# LAN8870_PINOUT.net
KiCad netlist of a schematic drawn in Altium Designer
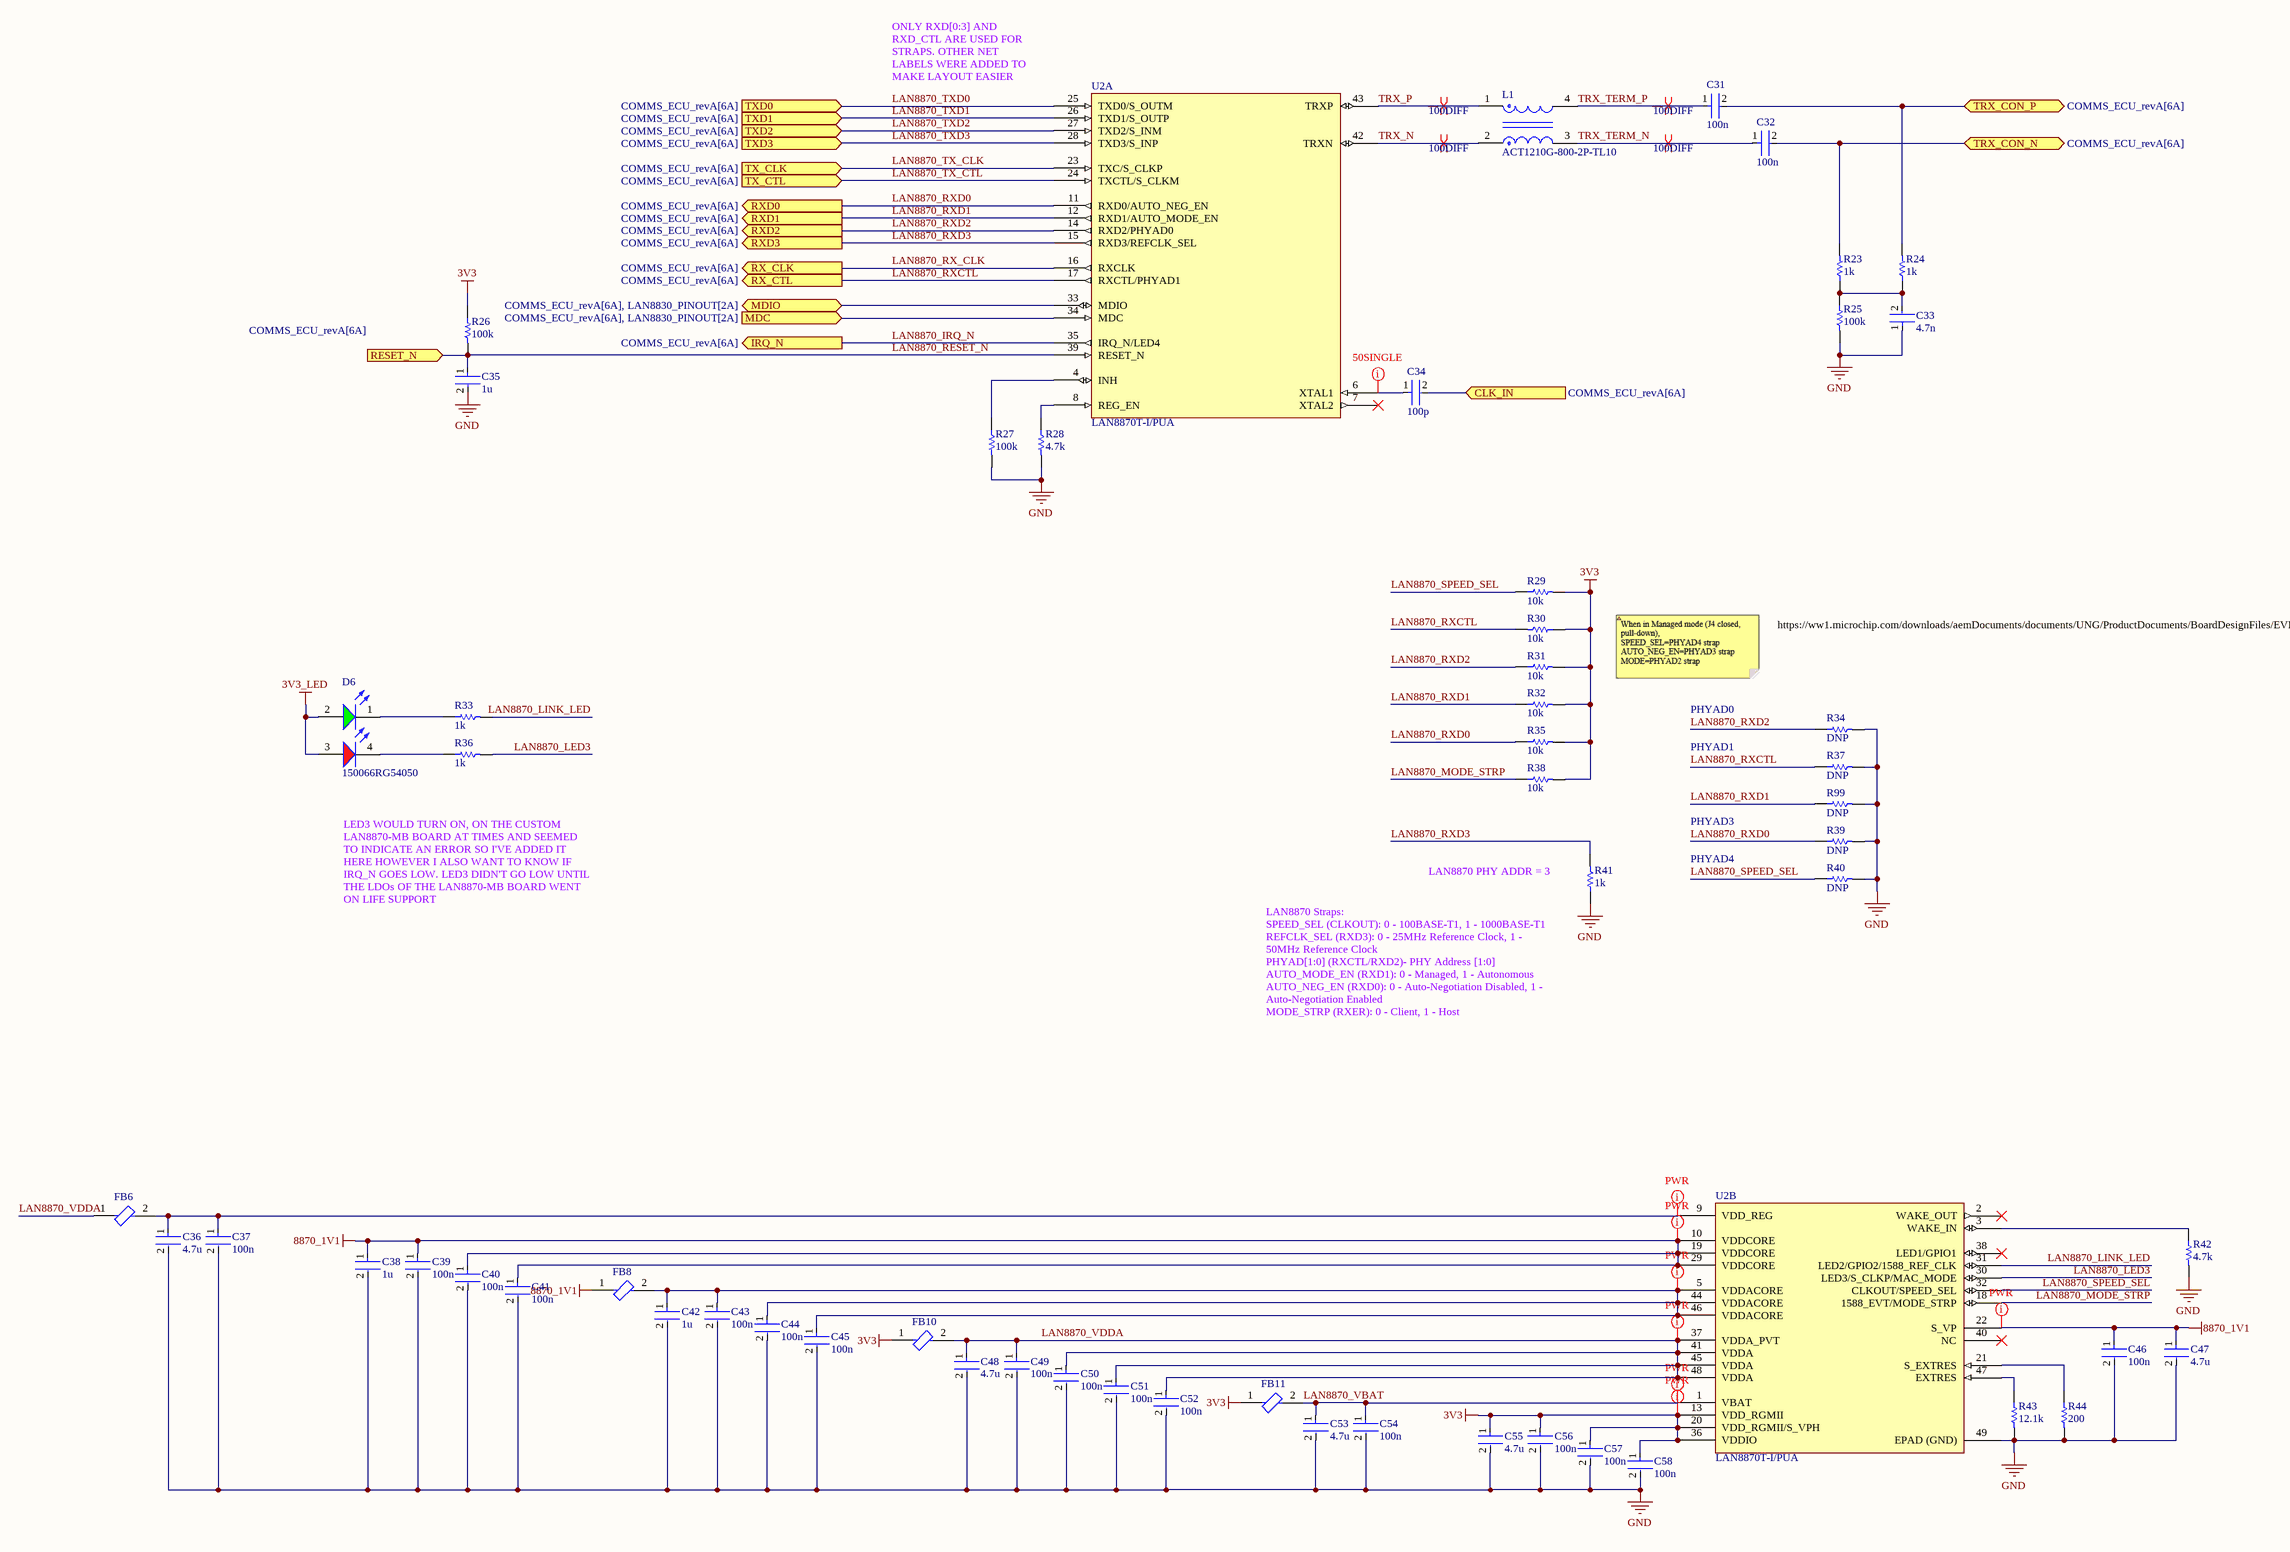
[diagram p0: LAN8870_PINOUT.SchDoc]

(export (version "E")
  (design (tool "Eeschema 10.0.6"))
  (components
    (comp (ref "C31")
      (value "100n")
      (footprint "FP-0402-L_1_0_0_05-W_0_5-IPC_A")
      (description "LARGE PADS, 0402 CAP, CHANGE COMMENT TO MATCH REAL P/N")
      (libsource (lib "Space Concordia") (part "b4654b650e69147ec39a6b967a45e02"))
    )
    (comp (ref "C32")
      (value "100n")
      (footprint "FP-0402-L_1_0_0_05-W_0_5-IPC_A")
      (description "LARGE PADS, 0402 CAP, CHANGE COMMENT TO MATCH REAL P/N")
      (libsource (lib "Space Concordia") (part "b4654b650e69147ec39a6b967a45e02"))
    )
    (comp (ref "C33")
      (value "4.7n")
      (footprint "FP-0402-L_1_0_0_05-W_0_5-IPC_A")
      (description "LARGE PADS, 0402 CAP, CHANGE COMMENT TO MATCH REAL P/N")
      (libsource (lib "Space Concordia") (part "b4654b650e69147ec39a6b967a45e02"))
    )
    (comp (ref "C34")
      (value "100p")
      (footprint "FP-0402-L_1_0_0_05-W_0_5-IPC_A")
      (description "LARGE PADS, 0402 CAP, CHANGE COMMENT TO MATCH REAL P/N")
      (libsource (lib "Space Concordia") (part "b4654b650e69147ec39a6b967a45e02"))
    )
    (comp (ref "C35")
      (value "1u")
      (footprint "FP-0402-L_1_0_0_05-W_0_5-IPC_A")
      (description "LARGE PADS, 0402 CAP, CHANGE COMMENT TO MATCH REAL P/N")
      (libsource (lib "Space Concordia") (part "b4654b650e69147ec39a6b967a45e02"))
    )
    (comp (ref "C36")
      (value "4.7u")
      (footprint "FP-0402-L_1_0_0_05-W_0_5-IPC_A")
      (description "LARGE PADS, 0402 CAP, CHANGE COMMENT TO MATCH REAL P/N")
      (libsource (lib "Space Concordia") (part "b4654b650e69147ec39a6b967a45e02"))
    )
    (comp (ref "C37")
      (value "100n")
      (footprint "FP-0402-L_1_0_0_05-W_0_5-IPC_A")
      (description "LARGE PADS, 0402 CAP, CHANGE COMMENT TO MATCH REAL P/N")
      (libsource (lib "Space Concordia") (part "b4654b650e69147ec39a6b967a45e02"))
    )
    (comp (ref "C38")
      (value "1u")
      (footprint "FP-0402-L_1_0_0_05-W_0_5-IPC_A")
      (description "LARGE PADS, 0402 CAP, CHANGE COMMENT TO MATCH REAL P/N")
      (libsource (lib "Space Concordia") (part "b4654b650e69147ec39a6b967a45e02"))
    )
    (comp (ref "C39")
      (value "100n")
      (footprint "FP-0402-L_1_0_0_05-W_0_5-IPC_A")
      (description "LARGE PADS, 0402 CAP, CHANGE COMMENT TO MATCH REAL P/N")
      (libsource (lib "Space Concordia") (part "b4654b650e69147ec39a6b967a45e02"))
    )
    (comp (ref "C40")
      (value "100n")
      (footprint "FP-0402-L_1_0_0_05-W_0_5-IPC_A")
      (description "LARGE PADS, 0402 CAP, CHANGE COMMENT TO MATCH REAL P/N")
      (libsource (lib "Space Concordia") (part "b4654b650e69147ec39a6b967a45e02"))
    )
    (comp (ref "C41")
      (value "100n")
      (footprint "FP-0402-L_1_0_0_05-W_0_5-IPC_A")
      (description "LARGE PADS, 0402 CAP, CHANGE COMMENT TO MATCH REAL P/N")
      (libsource (lib "Space Concordia") (part "b4654b650e69147ec39a6b967a45e02"))
    )
    (comp (ref "C42")
      (value "1u")
      (footprint "FP-0402-L_1_0_0_05-W_0_5-IPC_A")
      (description "LARGE PADS, 0402 CAP, CHANGE COMMENT TO MATCH REAL P/N")
      (libsource (lib "Space Concordia") (part "b4654b650e69147ec39a6b967a45e02"))
    )
    (comp (ref "C43")
      (value "100n")
      (footprint "FP-0402-L_1_0_0_05-W_0_5-IPC_A")
      (description "LARGE PADS, 0402 CAP, CHANGE COMMENT TO MATCH REAL P/N")
      (libsource (lib "Space Concordia") (part "b4654b650e69147ec39a6b967a45e02"))
    )
    (comp (ref "C44")
      (value "100n")
      (footprint "FP-0402-L_1_0_0_05-W_0_5-IPC_A")
      (description "LARGE PADS, 0402 CAP, CHANGE COMMENT TO MATCH REAL P/N")
      (libsource (lib "Space Concordia") (part "b4654b650e69147ec39a6b967a45e02"))
    )
    (comp (ref "C45")
      (value "100n")
      (footprint "FP-0402-L_1_0_0_05-W_0_5-IPC_A")
      (description "LARGE PADS, 0402 CAP, CHANGE COMMENT TO MATCH REAL P/N")
      (libsource (lib "Space Concordia") (part "b4654b650e69147ec39a6b967a45e02"))
    )
    (comp (ref "C46")
      (value "100n")
      (footprint "FP-0402-L_1_0_0_05-W_0_5-IPC_A")
      (description "LARGE PADS, 0402 CAP, CHANGE COMMENT TO MATCH REAL P/N")
      (libsource (lib "Space Concordia") (part "b4654b650e69147ec39a6b967a45e02"))
    )
    (comp (ref "C47")
      (value "4.7u")
      (footprint "FP-0402-L_1_0_0_05-W_0_5-IPC_A")
      (description "LARGE PADS, 0402 CAP, CHANGE COMMENT TO MATCH REAL P/N")
      (libsource (lib "Space Concordia") (part "b4654b650e69147ec39a6b967a45e02"))
    )
    (comp (ref "C48")
      (value "4.7u")
      (footprint "FP-0402-L_1_0_0_05-W_0_5-IPC_A")
      (description "LARGE PADS, 0402 CAP, CHANGE COMMENT TO MATCH REAL P/N")
      (libsource (lib "Space Concordia") (part "b4654b650e69147ec39a6b967a45e02"))
    )
    (comp (ref "C49")
      (value "100n")
      (footprint "FP-0402-L_1_0_0_05-W_0_5-IPC_A")
      (description "LARGE PADS, 0402 CAP, CHANGE COMMENT TO MATCH REAL P/N")
      (libsource (lib "Space Concordia") (part "b4654b650e69147ec39a6b967a45e02"))
    )
    (comp (ref "C50")
      (value "100n")
      (footprint "FP-0402-L_1_0_0_05-W_0_5-IPC_A")
      (description "LARGE PADS, 0402 CAP, CHANGE COMMENT TO MATCH REAL P/N")
      (libsource (lib "Space Concordia") (part "b4654b650e69147ec39a6b967a45e02"))
    )
    (comp (ref "C51")
      (value "100n")
      (footprint "FP-0402-L_1_0_0_05-W_0_5-IPC_A")
      (description "LARGE PADS, 0402 CAP, CHANGE COMMENT TO MATCH REAL P/N")
      (libsource (lib "Space Concordia") (part "b4654b650e69147ec39a6b967a45e02"))
    )
    (comp (ref "C52")
      (value "100n")
      (footprint "FP-0402-L_1_0_0_05-W_0_5-IPC_A")
      (description "LARGE PADS, 0402 CAP, CHANGE COMMENT TO MATCH REAL P/N")
      (libsource (lib "Space Concordia") (part "b4654b650e69147ec39a6b967a45e02"))
    )
    (comp (ref "C53")
      (value "4.7u")
      (footprint "FP-0402-L_1_0_0_05-W_0_5-IPC_A")
      (description "LARGE PADS, 0402 CAP, CHANGE COMMENT TO MATCH REAL P/N")
      (libsource (lib "Space Concordia") (part "b4654b650e69147ec39a6b967a45e02"))
    )
    (comp (ref "C54")
      (value "100n")
      (footprint "FP-0402-L_1_0_0_05-W_0_5-IPC_A")
      (description "LARGE PADS, 0402 CAP, CHANGE COMMENT TO MATCH REAL P/N")
      (libsource (lib "Space Concordia") (part "b4654b650e69147ec39a6b967a45e02"))
    )
    (comp (ref "C55")
      (value "4.7u")
      (footprint "FP-0402-L_1_0_0_05-W_0_5-IPC_A")
      (description "LARGE PADS, 0402 CAP, CHANGE COMMENT TO MATCH REAL P/N")
      (libsource (lib "Space Concordia") (part "b4654b650e69147ec39a6b967a45e02"))
    )
    (comp (ref "C56")
      (value "100n")
      (footprint "FP-0402-L_1_0_0_05-W_0_5-IPC_A")
      (description "LARGE PADS, 0402 CAP, CHANGE COMMENT TO MATCH REAL P/N")
      (libsource (lib "Space Concordia") (part "b4654b650e69147ec39a6b967a45e02"))
    )
    (comp (ref "C57")
      (value "100n")
      (footprint "FP-0402-L_1_0_0_05-W_0_5-IPC_A")
      (description "LARGE PADS, 0402 CAP, CHANGE COMMENT TO MATCH REAL P/N")
      (libsource (lib "Space Concordia") (part "b4654b650e69147ec39a6b967a45e02"))
    )
    (comp (ref "C58")
      (value "100n")
      (footprint "FP-0402-L_1_0_0_05-W_0_5-IPC_A")
      (description "LARGE PADS, 0402 CAP, CHANGE COMMENT TO MATCH REAL P/N")
      (libsource (lib "Space Concordia") (part "b4654b650e69147ec39a6b967a45e02"))
    )
    (comp (ref "D6")
      (value "150066RG54050")
      (footprint "WL-SBCD_0606")
      (description "Led, Red/Grn, 180Mcd/230Mcd, 624Nm/525Nm Rohs Compliant: Yes")
      (fields (field (name "SOURCE") "rgled.SchLib"))
      (libsource (lib "Space Concordia") (part "CMP-004-00034-2"))
    )
    (comp (ref "FB6")
      (value "BLM18KG331SH1D")
      (footprint "FP-BLM18-0_15-t0_8-IPC_B")
      (description "Chip Ferrite Bead, 0603, 330Ω @ 100MHz, 0.08Ω, 25%, 1.7A")
      (libsource (lib "Altium Content Vault") (part "5f30dd21d616792df468990f7003faa"))
    )
    (comp (ref "FB8")
      (value "BLM18KG331SH1D")
      (footprint "FP-BLM18-0_15-t0_8-IPC_B")
      (description "Chip Ferrite Bead, 0603, 330Ω @ 100MHz, 0.08Ω, 25%, 1.7A")
      (libsource (lib "Altium Content Vault") (part "5f30dd21d616792df468990f7003faa"))
    )
    (comp (ref "FB10")
      (value "BLM18KG331SH1D")
      (footprint "FP-BLM18-0_15-t0_8-IPC_B")
      (description "Chip Ferrite Bead, 0603, 330Ω @ 100MHz, 0.08Ω, 25%, 1.7A")
      (libsource (lib "Altium Content Vault") (part "5f30dd21d616792df468990f7003faa"))
    )
    (comp (ref "FB11")
      (value "BLM18KG331SH1D")
      (footprint "FP-BLM18-0_15-t0_8-IPC_B")
      (description "Chip Ferrite Bead, 0603, 330Ω @ 100MHz, 0.08Ω, 25%, 1.7A")
      (libsource (lib "Altium Content Vault") (part "5f30dd21d616792df468990f7003faa"))
    )
    (comp (ref "L1")
      (value "ACT1210G-800-2P-TL10")
      (footprint "FP-ACT1210G-800-2P-TL10-MFG")
      (description "CMC 80UH 70MA 2LN 3.8KOHM SMD")
      (libsource (lib "Altium Content Vault") (part "b4b74a627ea9af473eaab86227aab92"))
    )
    (comp (ref "R23")
      (value "1k")
      (footprint "R0603B")
      (description "Resistor")
      (libsource (lib "Space Concordia") (part "Resistor"))
    )
    (comp (ref "R24")
      (value "1k")
      (footprint "R0603B")
      (description "Resistor")
      (libsource (lib "Space Concordia") (part "Resistor"))
    )
    (comp (ref "R25")
      (value "100k")
      (footprint "R0603B")
      (description "Resistor")
      (libsource (lib "Space Concordia") (part "Resistor"))
    )
    (comp (ref "R26")
      (value "100k")
      (footprint "R0603B")
      (description "Resistor")
      (libsource (lib "Space Concordia") (part "Resistor"))
    )
    (comp (ref "R27")
      (value "100k")
      (footprint "R0603B")
      (description "Resistor")
      (libsource (lib "Space Concordia") (part "Resistor"))
    )
    (comp (ref "R28")
      (value "4.7k")
      (footprint "R0603B")
      (description "Resistor")
      (libsource (lib "Space Concordia") (part "Resistor"))
    )
    (comp (ref "R29")
      (value "10k")
      (footprint "R0603B")
      (description "Resistor")
      (libsource (lib "Space Concordia") (part "Resistor"))
    )
    (comp (ref "R30")
      (value "10k")
      (footprint "R0603B")
      (description "Resistor")
      (libsource (lib "Space Concordia") (part "Resistor"))
    )
    (comp (ref "R31")
      (value "10k")
      (footprint "R0603B")
      (description "Resistor")
      (libsource (lib "Space Concordia") (part "Resistor"))
    )
    (comp (ref "R32")
      (value "10k")
      (footprint "R0603B")
      (description "Resistor")
      (libsource (lib "Space Concordia") (part "Resistor"))
    )
    (comp (ref "R33")
      (value "1k")
      (footprint "R0603B")
      (description "Resistor")
      (libsource (lib "Space Concordia") (part "Resistor"))
    )
    (comp (ref "R34")
      (value "DNP")
      (footprint "R0603B")
      (description "Resistor")
      (libsource (lib "Space Concordia") (part "Resistor"))
    )
    (comp (ref "R35")
      (value "10k")
      (footprint "R0603B")
      (description "Resistor")
      (libsource (lib "Space Concordia") (part "Resistor"))
    )
    (comp (ref "R36")
      (value "1k")
      (footprint "R0603B")
      (description "Resistor")
      (libsource (lib "Space Concordia") (part "Resistor"))
    )
    (comp (ref "R37")
      (value "DNP")
      (footprint "R0603B")
      (description "Resistor")
      (libsource (lib "Space Concordia") (part "Resistor"))
    )
    (comp (ref "R38")
      (value "10k")
      (footprint "R0603B")
      (description "Resistor")
      (libsource (lib "Space Concordia") (part "Resistor"))
    )
    (comp (ref "R39")
      (value "DNP")
      (footprint "R0603B")
      (description "Resistor")
      (libsource (lib "Space Concordia") (part "Resistor"))
    )
    (comp (ref "R40")
      (value "DNP")
      (footprint "R0603B")
      (description "Resistor")
      (libsource (lib "Space Concordia") (part "Resistor"))
    )
    (comp (ref "R41")
      (value "1k")
      (footprint "R0603B")
      (description "Resistor")
      (libsource (lib "Space Concordia") (part "Resistor"))
    )
    (comp (ref "R42")
      (value "4.7k")
      (footprint "R0603B")
      (description "Resistor")
      (libsource (lib "Space Concordia") (part "Resistor"))
    )
    (comp (ref "R43")
      (value "12.1k")
      (footprint "R0603B")
      (description "Resistor")
      (libsource (lib "Space Concordia") (part "Resistor"))
    )
    (comp (ref "R44")
      (value "200")
      (footprint "R0603B")
      (description "Resistor")
      (libsource (lib "Space Concordia") (part "Resistor"))
    )
    (comp (ref "R99")
      (value "DNP")
      (footprint "R0603B")
      (description "Resistor")
      (libsource (lib "Space Concordia") (part "Resistor"))
    )
    (comp (ref "U2")
      (value "LAN8870T-I/PUA")
      (footprint "QFN50P700X700X100_HS-49N")
      (description "100/1000BASE-T1 Rgmii/sgmii Phy")
      (libsource (lib "Space Concordia") (part "LAN8870T-I_PUA"))
    )
  )
  (nets
    (net (code "1") (name "/CLK_IN") (class "Default")
      (node (ref "C34") (pin "2") (pinfunction "2_2") (pintype "passive"))
    )
    (net (code "2") (name "/LAN8870_IRQ_N") (class "Default")
      (node (ref "U2") (pin "35") (pinfunction "IRQ_N/LED4_35") (pintype "output"))
    )
    (net (code "3") (name "/LAN8870_LED3") (class "Default")
      (node (ref "R36") (pin "2") (pinfunction "2_2") (pintype "passive"))
      (node (ref "U2") (pin "30") (pinfunction "LED3/S_CLKP/MAC_MODE_30") (pintype "bidirectional"))
    )
    (net (code "4") (name "/LAN8870_LINK_LED") (class "Default")
      (node (ref "R33") (pin "2") (pinfunction "2_2") (pintype "passive"))
      (node (ref "U2") (pin "31") (pinfunction "LED2/GPIO2/1588_REF_CLK_31") (pintype "bidirectional"))
    )
    (net (code "5") (name "/LAN8870_MODE_STRP") (class "Default")
      (node (ref "R38") (pin "1") (pinfunction "1_1") (pintype "passive"))
      (node (ref "U2") (pin "18") (pinfunction "1588_EVT/MODE_STRP_18") (pintype "bidirectional"))
    )
    (net (code "6") (name "/LAN8870_RESET_N") (class "Default")
      (node (ref "C35") (pin "1") (pinfunction "1_1") (pintype "passive"))
      (node (ref "R26") (pin "2") (pinfunction "2_2") (pintype "passive"))
      (node (ref "U2") (pin "39") (pinfunction "RESET_N_39") (pintype "input"))
    )
    (net (code "7") (name "/LAN8870_RXCTL") (class "Default")
      (node (ref "R30") (pin "2") (pinfunction "2_2") (pintype "passive"))
      (node (ref "R37") (pin "1") (pinfunction "1_1") (pintype "passive"))
      (node (ref "U2") (pin "17") (pinfunction "RXCTL/PHYAD1_17") (pintype "output"))
    )
    (net (code "8") (name "/LAN8870_RXD0") (class "Default")
      (node (ref "R35") (pin "1") (pinfunction "1_1") (pintype "passive"))
      (node (ref "R39") (pin "1") (pinfunction "1_1") (pintype "passive"))
      (node (ref "U2") (pin "11") (pinfunction "RXD0/AUTO_NEG_EN_11") (pintype "output"))
    )
    (net (code "9") (name "/LAN8870_RXD1") (class "Default")
      (node (ref "R32") (pin "1") (pinfunction "1_1") (pintype "passive"))
      (node (ref "R99") (pin "1") (pinfunction "1_1") (pintype "passive"))
      (node (ref "U2") (pin "12") (pinfunction "RXD1/AUTO_MODE_EN_12") (pintype "output"))
    )
    (net (code "10") (name "/LAN8870_RXD2") (class "Default")
      (node (ref "R31") (pin "1") (pinfunction "1_1") (pintype "passive"))
      (node (ref "R34") (pin "1") (pinfunction "1_1") (pintype "passive"))
      (node (ref "U2") (pin "14") (pinfunction "RXD2/PHYAD0_14") (pintype "output"))
    )
    (net (code "11") (name "/LAN8870_RXD3") (class "Default")
      (node (ref "R41") (pin "2") (pinfunction "2_2") (pintype "passive"))
      (node (ref "U2") (pin "15") (pinfunction "RXD3/REFCLK_SEL_15") (pintype "output"))
    )
    (net (code "12") (name "/LAN8870_RX_CLK") (class "Default")
      (node (ref "U2") (pin "16") (pinfunction "RXCLK_16") (pintype "output"))
    )
    (net (code "13") (name "/LAN8870_SPEED_SEL") (class "Default")
      (node (ref "R29") (pin "1") (pinfunction "1_1") (pintype "passive"))
      (node (ref "R40") (pin "1") (pinfunction "1_1") (pintype "passive"))
      (node (ref "U2") (pin "32") (pinfunction "CLKOUT/SPEED_SEL_32") (pintype "bidirectional"))
    )
    (net (code "14") (name "/LAN8870_TXD0") (class "Default")
      (node (ref "U2") (pin "25") (pinfunction "TXD0/S_OUTM_25") (pintype "input"))
    )
    (net (code "15") (name "/LAN8870_TXD1") (class "Default")
      (node (ref "U2") (pin "26") (pinfunction "TXD1/S_OUTP_26") (pintype "input"))
    )
    (net (code "16") (name "/LAN8870_TXD2") (class "Default")
      (node (ref "U2") (pin "27") (pinfunction "TXD2/S_INM_27") (pintype "input"))
    )
    (net (code "17") (name "/LAN8870_TXD3") (class "Default")
      (node (ref "U2") (pin "28") (pinfunction "TXD3/S_INP_28") (pintype "input"))
    )
    (net (code "18") (name "/LAN8870_TX_CLK") (class "Default")
      (node (ref "U2") (pin "23") (pinfunction "TXC/S_CLKP_23") (pintype "input"))
    )
    (net (code "19") (name "/LAN8870_TX_CTL") (class "Default")
      (node (ref "U2") (pin "24") (pinfunction "TXCTL/S_CLKM_24") (pintype "input"))
    )
    (net (code "20") (name "/LAN8870_VBAT") (class "Default")
      (node (ref "C53") (pin "1") (pinfunction "1_1") (pintype "passive"))
      (node (ref "C54") (pin "1") (pinfunction "1_1") (pintype "passive"))
      (node (ref "FB11") (pin "2") (pinfunction "2_2") (pintype "passive"))
      (node (ref "U2") (pin "1") (pinfunction "VBAT_1") (pintype "power_in"))
    )
    (net (code "21") (name "/LAN8870_VDDA") (class "Default")
      (node (ref "C48") (pin "1") (pinfunction "1_1") (pintype "passive"))
      (node (ref "C49") (pin "1") (pinfunction "1_1") (pintype "passive"))
      (node (ref "C50") (pin "1") (pinfunction "1_1") (pintype "passive"))
      (node (ref "C51") (pin "1") (pinfunction "1_1") (pintype "passive"))
      (node (ref "C52") (pin "1") (pinfunction "1_1") (pintype "passive"))
      (node (ref "FB10") (pin "2") (pinfunction "2_2") (pintype "passive"))
      (node (ref "FB6") (pin "1") (pinfunction "1_1") (pintype "passive"))
      (node (ref "U2") (pin "37") (pinfunction "VDDA_PVT_37") (pintype "power_in"))
      (node (ref "U2") (pin "41") (pinfunction "VDDA_41") (pintype "power_in"))
      (node (ref "U2") (pin "45") (pinfunction "VDDA_45") (pintype "power_in"))
      (node (ref "U2") (pin "48") (pinfunction "VDDA_48") (pintype "power_in"))
    )
    (net (code "22") (name "/MDC") (class "Default")
      (node (ref "U2") (pin "34") (pinfunction "MDC_34") (pintype "input"))
    )
    (net (code "23") (name "/MDIO") (class "Default")
      (node (ref "U2") (pin "33") (pinfunction "MDIO_33") (pintype "bidirectional"))
    )
    (net (code "24") (name "/TRX_CON_N") (class "Default")
      (node (ref "C32") (pin "2") (pinfunction "2_2") (pintype "passive"))
      (node (ref "R23") (pin "2") (pinfunction "2_2") (pintype "passive"))
    )
    (net (code "25") (name "/TRX_CON_P") (class "Default")
      (node (ref "C31") (pin "2") (pinfunction "2_2") (pintype "passive"))
      (node (ref "R24") (pin "2") (pinfunction "2_2") (pintype "passive"))
    )
    (net (code "26") (name "/TRX_N") (class "Default")
      (node (ref "L1") (pin "2") (pinfunction "2_2") (pintype "passive"))
      (node (ref "U2") (pin "42") (pinfunction "TRXN_42") (pintype "bidirectional"))
    )
    (net (code "27") (name "/TRX_P") (class "Default")
      (node (ref "L1") (pin "1") (pinfunction "1_1") (pintype "passive"))
      (node (ref "U2") (pin "43") (pinfunction "TRXP_43") (pintype "bidirectional"))
    )
    (net (code "28") (name "/TRX_TERM_N") (class "Default")
      (node (ref "C32") (pin "1") (pinfunction "1_1") (pintype "passive"))
      (node (ref "L1") (pin "3") (pinfunction "3_3") (pintype "passive"))
    )
    (net (code "29") (name "/TRX_TERM_P") (class "Default")
      (node (ref "C31") (pin "1") (pinfunction "1_1") (pintype "passive"))
      (node (ref "L1") (pin "4") (pinfunction "4_4") (pintype "passive"))
    )
    (net (code "30") (name "3V3") (class "Default")
      (node (ref "C55") (pin "1") (pinfunction "1_1") (pintype "passive"))
      (node (ref "C56") (pin "1") (pinfunction "1_1") (pintype "passive"))
      (node (ref "C57") (pin "1") (pinfunction "1_1") (pintype "passive"))
      (node (ref "C58") (pin "1") (pinfunction "1_1") (pintype "passive"))
      (node (ref "FB10") (pin "1") (pinfunction "1_1") (pintype "passive"))
      (node (ref "FB11") (pin "1") (pinfunction "1_1") (pintype "passive"))
      (node (ref "R26") (pin "1") (pinfunction "1_1") (pintype "passive"))
      (node (ref "R29") (pin "2") (pinfunction "2_2") (pintype "passive"))
      (node (ref "R30") (pin "1") (pinfunction "1_1") (pintype "passive"))
      (node (ref "R31") (pin "2") (pinfunction "2_2") (pintype "passive"))
      (node (ref "R32") (pin "2") (pinfunction "2_2") (pintype "passive"))
      (node (ref "R35") (pin "2") (pinfunction "2_2") (pintype "passive"))
      (node (ref "R38") (pin "2") (pinfunction "2_2") (pintype "passive"))
      (node (ref "U2") (pin "13") (pinfunction "VDD_RGMII_13") (pintype "power_in"))
      (node (ref "U2") (pin "20") (pinfunction "VDD_RGMII/S_VPH_20") (pintype "power_in"))
      (node (ref "U2") (pin "36") (pinfunction "VDDIO_36") (pintype "power_in"))
    )
    (net (code "31") (name "3V3_LED") (class "Default")
      (node (ref "D6") (pin "2") (pinfunction "A_2") (pintype "passive"))
      (node (ref "D6") (pin "3") (pinfunction "A_3") (pintype "passive"))
    )
    (net (code "32") (name "8870_1V1") (class "Default")
      (node (ref "C38") (pin "1") (pinfunction "1_1") (pintype "passive"))
      (node (ref "C39") (pin "1") (pinfunction "1_1") (pintype "passive"))
      (node (ref "C40") (pin "1") (pinfunction "1_1") (pintype "passive"))
      (node (ref "C41") (pin "1") (pinfunction "1_1") (pintype "passive"))
      (node (ref "C46") (pin "1") (pinfunction "1_1") (pintype "passive"))
      (node (ref "C47") (pin "1") (pinfunction "1_1") (pintype "passive"))
      (node (ref "FB8") (pin "1") (pinfunction "1_1") (pintype "passive"))
      (node (ref "U2") (pin "10") (pinfunction "VDDCORE_10") (pintype "power_in"))
      (node (ref "U2") (pin "19") (pinfunction "VDDCORE_19") (pintype "power_in"))
      (node (ref "U2") (pin "22") (pinfunction "S_VP_22") (pintype "passive"))
      (node (ref "U2") (pin "29") (pinfunction "VDDCORE_29") (pintype "power_in"))
    )
    (net (code "33") (name "GND") (class "Default")
      (node (ref "C33") (pin "1") (pinfunction "1_1") (pintype "passive"))
      (node (ref "C35") (pin "2") (pinfunction "2_2") (pintype "passive"))
      (node (ref "C36") (pin "2") (pinfunction "2_2") (pintype "passive"))
      (node (ref "C37") (pin "2") (pinfunction "2_2") (pintype "passive"))
      (node (ref "C38") (pin "2") (pinfunction "2_2") (pintype "passive"))
      (node (ref "C39") (pin "2") (pinfunction "2_2") (pintype "passive"))
      (node (ref "C40") (pin "2") (pinfunction "2_2") (pintype "passive"))
      (node (ref "C41") (pin "2") (pinfunction "2_2") (pintype "passive"))
      (node (ref "C42") (pin "2") (pinfunction "2_2") (pintype "passive"))
      (node (ref "C43") (pin "2") (pinfunction "2_2") (pintype "passive"))
      (node (ref "C44") (pin "2") (pinfunction "2_2") (pintype "passive"))
      (node (ref "C45") (pin "2") (pinfunction "2_2") (pintype "passive"))
      (node (ref "C46") (pin "2") (pinfunction "2_2") (pintype "passive"))
      (node (ref "C47") (pin "2") (pinfunction "2_2") (pintype "passive"))
      (node (ref "C48") (pin "2") (pinfunction "2_2") (pintype "passive"))
      (node (ref "C49") (pin "2") (pinfunction "2_2") (pintype "passive"))
      (node (ref "C50") (pin "2") (pinfunction "2_2") (pintype "passive"))
      (node (ref "C51") (pin "2") (pinfunction "2_2") (pintype "passive"))
      (node (ref "C52") (pin "2") (pinfunction "2_2") (pintype "passive"))
      (node (ref "C53") (pin "2") (pinfunction "2_2") (pintype "passive"))
      (node (ref "C54") (pin "2") (pinfunction "2_2") (pintype "passive"))
      (node (ref "C55") (pin "2") (pinfunction "2_2") (pintype "passive"))
      (node (ref "C56") (pin "2") (pinfunction "2_2") (pintype "passive"))
      (node (ref "C57") (pin "2") (pinfunction "2_2") (pintype "passive"))
      (node (ref "C58") (pin "2") (pinfunction "2_2") (pintype "passive"))
      (node (ref "R25") (pin "2") (pinfunction "2_2") (pintype "passive"))
      (node (ref "R27") (pin "2") (pinfunction "2_2") (pintype "passive"))
      (node (ref "R28") (pin "2") (pinfunction "2_2") (pintype "passive"))
      (node (ref "R34") (pin "2") (pinfunction "2_2") (pintype "passive"))
      (node (ref "R37") (pin "2") (pinfunction "2_2") (pintype "passive"))
      (node (ref "R39") (pin "2") (pinfunction "2_2") (pintype "passive"))
      (node (ref "R40") (pin "2") (pinfunction "2_2") (pintype "passive"))
      (node (ref "R41") (pin "1") (pinfunction "1_1") (pintype "passive"))
      (node (ref "R42") (pin "2") (pinfunction "2_2") (pintype "passive"))
      (node (ref "R43") (pin "2") (pinfunction "2_2") (pintype "passive"))
      (node (ref "R44") (pin "2") (pinfunction "2_2") (pintype "passive"))
      (node (ref "R99") (pin "2") (pinfunction "2_2") (pintype "passive"))
      (node (ref "U2") (pin "49") (pinfunction "EPAD_(GND)_49") (pintype "power_in"))
    )
    (net (code "34") (name "Net-(C33-Pad2)") (class "Default")
      (node (ref "C33") (pin "2") (pinfunction "2_2") (pintype "passive"))
      (node (ref "R23") (pin "1") (pinfunction "1_1") (pintype "passive"))
      (node (ref "R24") (pin "1") (pinfunction "1_1") (pintype "passive"))
      (node (ref "R25") (pin "1") (pinfunction "1_1") (pintype "passive"))
    )
    (net (code "35") (name "Net-(C42-Pad1)") (class "Default")
      (node (ref "C42") (pin "1") (pinfunction "1_1") (pintype "passive"))
      (node (ref "C43") (pin "1") (pinfunction "1_1") (pintype "passive"))
      (node (ref "C44") (pin "1") (pinfunction "1_1") (pintype "passive"))
      (node (ref "C45") (pin "1") (pinfunction "1_1") (pintype "passive"))
      (node (ref "FB8") (pin "2") (pinfunction "2_2") (pintype "passive"))
      (node (ref "U2") (pin "44") (pinfunction "VDDACORE_44") (pintype "power_in"))
      (node (ref "U2") (pin "46") (pinfunction "VDDACORE_46") (pintype "power_in"))
      (node (ref "U2") (pin "5") (pinfunction "VDDACORE_5") (pintype "power_in"))
    )
    (net (code "36") (name "Net-(D6-K-Pad1)") (class "Default")
      (node (ref "D6") (pin "1") (pinfunction "K_1") (pintype "passive"))
      (node (ref "R33") (pin "1") (pinfunction "1_1") (pintype "passive"))
    )
    (net (code "37") (name "Net-(D6-K-Pad4)") (class "Default")
      (node (ref "D6") (pin "4") (pinfunction "K_4") (pintype "passive"))
      (node (ref "R36") (pin "1") (pinfunction "1_1") (pintype "passive"))
    )
    (net (code "38") (name "Net-(U2A-INH)") (class "Default")
      (node (ref "R27") (pin "1") (pinfunction "1_1") (pintype "passive"))
      (node (ref "U2") (pin "4") (pinfunction "INH_4") (pintype "bidirectional"))
    )
    (net (code "39") (name "Net-(U2A-REG_EN)") (class "Default")
      (node (ref "R28") (pin "1") (pinfunction "1_1") (pintype "passive"))
      (node (ref "U2") (pin "8") (pinfunction "REG_EN_8") (pintype "input"))
    )
    (net (code "40") (name "Net-(U2A-XTAL1)") (class "Default")
      (node (ref "C34") (pin "1") (pinfunction "1_1") (pintype "passive"))
      (node (ref "U2") (pin "6") (pinfunction "XTAL1_6") (pintype "input"))
    )
    (net (code "41") (name "Net-(U2B-EXTRES)") (class "Default")
      (node (ref "R43") (pin "1") (pinfunction "1_1") (pintype "passive"))
      (node (ref "U2") (pin "47") (pinfunction "EXTRES_47") (pintype "input"))
    )
    (net (code "42") (name "Net-(U2B-S_EXTRES)") (class "Default")
      (node (ref "R44") (pin "1") (pinfunction "1_1") (pintype "passive"))
      (node (ref "U2") (pin "21") (pinfunction "S_EXTRES_21") (pintype "input"))
    )
    (net (code "43") (name "Net-(U2B-VDD_REG)") (class "Default")
      (node (ref "C36") (pin "1") (pinfunction "1_1") (pintype "passive"))
      (node (ref "C37") (pin "1") (pinfunction "1_1") (pintype "passive"))
      (node (ref "FB6") (pin "2") (pinfunction "2_2") (pintype "passive"))
      (node (ref "U2") (pin "9") (pinfunction "VDD_REG_9") (pintype "power_in"))
    )
    (net (code "44") (name "Net-(U2B-WAKE_IN)") (class "Default")
      (node (ref "R42") (pin "1") (pinfunction "1_1") (pintype "passive"))
      (node (ref "U2") (pin "3") (pinfunction "WAKE_IN_3") (pintype "bidirectional"))
    )
    (net (code "45") (name "unconnected-(U2A-XTAL2-Pad7)") (class "Default")
      (node (ref "U2") (pin "7") (pinfunction "XTAL2_7") (pintype "output+no_connect"))
    )
    (net (code "46") (name "unconnected-(U2B-LED1{slash}GPIO1-Pad38)") (class "Default")
      (node (ref "U2") (pin "38") (pinfunction "LED1/GPIO1_38") (pintype "bidirectional+no_connect"))
    )
    (net (code "47") (name "unconnected-(U2B-NC-Pad40)") (class "Default")
      (node (ref "U2") (pin "40") (pinfunction "NC_40") (pintype "passive+no_connect"))
    )
    (net (code "48") (name "unconnected-(U2B-WAKE_OUT-Pad2)") (class "Default")
      (node (ref "U2") (pin "2") (pinfunction "WAKE_OUT_2") (pintype "output+no_connect"))
    )
  )
)
